# Power.net
KiCad netlist of a schematic drawn in Altium Designer
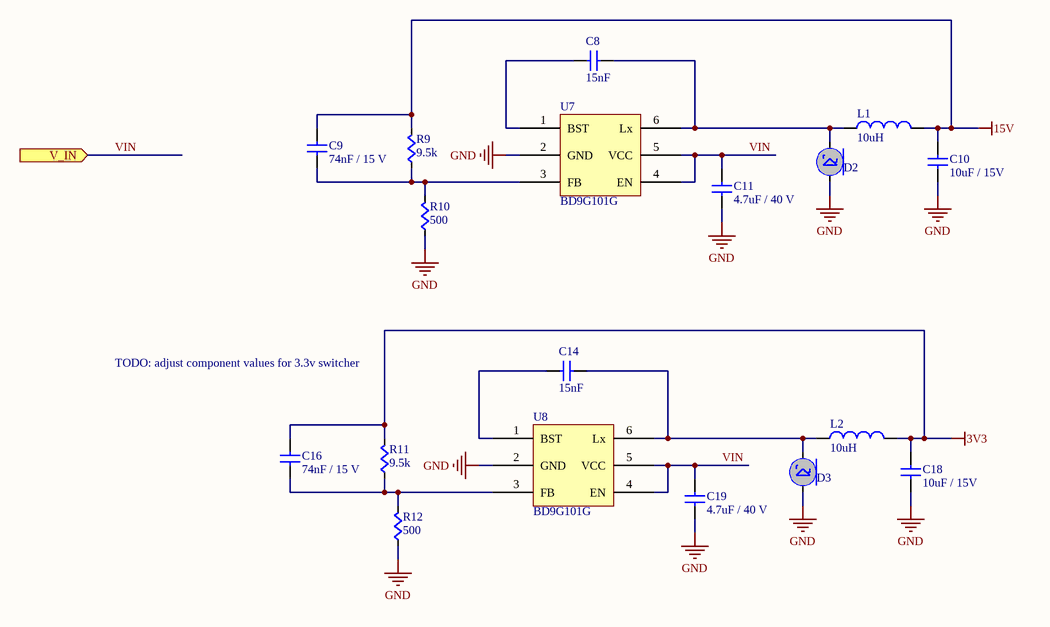
[diagram p0: Power.SchDoc]

(export (version "E")
  (design (tool "Eeschema 10.0.6"))
  (components
    (comp (ref "C8")
      (value "15nF")
      (footprint "CAPC0603")
      (fields (field (name "Comment") "Cap"))
      (libsource (lib "Passives") (part "Cap"))
    )
    (comp (ref "C9")
      (value "74nF / 15 V")
      (footprint "CAPC0603")
      (fields (field (name "Comment") "Cap"))
      (libsource (lib "Passives") (part "Cap"))
    )
    (comp (ref "C10")
      (value "10uF / 15V")
      (footprint "CAPC0805")
      (fields (field (name "Comment") "Cap"))
      (libsource (lib "Passives") (part "Cap"))
    )
    (comp (ref "C11")
      (value "4.7uF / 40 V")
      (footprint "CAPC0805")
      (fields (field (name "Comment") "Cap"))
      (libsource (lib "Passives") (part "Cap"))
    )
    (comp (ref "C14")
      (value "15nF")
      (footprint "CAPC0603")
      (fields (field (name "Comment") "Cap"))
      (libsource (lib "Passives") (part "Cap"))
    )
    (comp (ref "C16")
      (value "74nF / 15 V")
      (footprint "CAPC0603")
      (fields (field (name "Comment") "Cap"))
      (libsource (lib "Passives") (part "Cap"))
    )
    (comp (ref "C18")
      (value "10uF / 15V")
      (footprint "CAPC0805")
      (fields (field (name "Comment") "Cap"))
      (libsource (lib "Passives") (part "Cap"))
    )
    (comp (ref "C19")
      (value "4.7uF / 40 V")
      (footprint "CAPC0805")
      (fields (field (name "Comment") "Cap"))
      (libsource (lib "Passives") (part "Cap"))
    )
    (comp (ref "D2")
      (value "Schottky")
      (footprint "US1K-13-F")
      (description "Schottky Diode Template")
      (libsource (lib "Semiconductors") (part "Schottky"))
    )
    (comp (ref "D3")
      (value "Schottky")
      (footprint "US1K-13-F")
      (description "Schottky Diode Template")
      (libsource (lib "Semiconductors") (part "Schottky"))
    )
    (comp (ref "L1")
      (value "Inductor")
      (footprint "CAPC0805")
      (fields (field (name "INDUCTANCE") "10uH"))
      (libsource (lib "Passives") (part "Inductor"))
    )
    (comp (ref "L2")
      (value "Inductor")
      (footprint "CAPC0805")
      (fields (field (name "INDUCTANCE") "10uH"))
      (libsource (lib "Passives") (part "Inductor"))
    )
    (comp (ref "R9")
      (value "9.5k")
      (footprint "RES0603")
      (fields (field (name "Comment") "Res"))
      (libsource (lib "Passives") (part "Res"))
    )
    (comp (ref "R10")
      (value "500")
      (footprint "RES0603")
      (fields (field (name "Comment") "Res"))
      (libsource (lib "Passives") (part "Res"))
    )
    (comp (ref "R11")
      (value "9.5k")
      (footprint "RES0603")
      (fields (field (name "Comment") "Res"))
      (libsource (lib "Passives") (part "Res"))
    )
    (comp (ref "R12")
      (value "500")
      (footprint "RES0603")
      (fields (field (name "Comment") "Res"))
      (libsource (lib "Passives") (part "Res"))
    )
    (comp (ref "U7")
      (value "BD9G101G")
      (footprint "BD9G101G")
      (description "Simple Step-down Switching Regulators with Built-in Power MOSFET")
      (libsource (lib "ICs") (part "BD9G101G"))
    )
    (comp (ref "U8")
      (value "BD9G101G")
      (footprint "BD9G101G")
      (description "Simple Step-down Switching Regulators with Built-in Power MOSFET")
      (libsource (lib "ICs") (part "BD9G101G"))
    )
  )
  (nets
    (net (code "1") (name "/VIN") (class "Default")
      (node (ref "C11") (pin "1") (pinfunction "A_1") (pintype "passive"))
      (node (ref "C19") (pin "1") (pinfunction "A_1") (pintype "passive"))
      (node (ref "U7") (pin "4") (pinfunction "EN_4") (pintype "passive"))
      (node (ref "U7") (pin "5") (pinfunction "VCC_5") (pintype "passive"))
      (node (ref "U8") (pin "4") (pinfunction "EN_4") (pintype "passive"))
      (node (ref "U8") (pin "5") (pinfunction "VCC_5") (pintype "passive"))
    )
    (net (code "2") (name "3V3") (class "Default")
      (node (ref "C16") (pin "2") (pinfunction "B_2") (pintype "passive"))
      (node (ref "C18") (pin "1") (pinfunction "A_1") (pintype "passive"))
      (node (ref "L2") (pin "2") (pinfunction "B_2") (pintype "passive"))
      (node (ref "R11") (pin "1") (pinfunction "A_1") (pintype "passive"))
    )
    (net (code "3") (name "15V") (class "Default")
      (node (ref "C10") (pin "1") (pinfunction "A_1") (pintype "passive"))
      (node (ref "C9") (pin "2") (pinfunction "B_2") (pintype "passive"))
      (node (ref "L1") (pin "2") (pinfunction "B_2") (pintype "passive"))
      (node (ref "R9") (pin "1") (pinfunction "A_1") (pintype "passive"))
    )
    (net (code "4") (name "GND") (class "Default")
      (node (ref "C10") (pin "2") (pinfunction "B_2") (pintype "passive"))
      (node (ref "C11") (pin "2") (pinfunction "B_2") (pintype "passive"))
      (node (ref "C18") (pin "2") (pinfunction "B_2") (pintype "passive"))
      (node (ref "C19") (pin "2") (pinfunction "B_2") (pintype "passive"))
      (node (ref "D2") (pin "A") (pinfunction "A_A") (pintype "passive"))
      (node (ref "D3") (pin "A") (pinfunction "A_A") (pintype "passive"))
      (node (ref "R10") (pin "2") (pinfunction "B_2") (pintype "passive"))
      (node (ref "R12") (pin "2") (pinfunction "B_2") (pintype "passive"))
      (node (ref "U7") (pin "2") (pinfunction "GND_2") (pintype "passive"))
      (node (ref "U8") (pin "2") (pinfunction "GND_2") (pintype "passive"))
    )
    (net (code "5") (name "Net-(C8-A)") (class "Default")
      (node (ref "C8") (pin "1") (pinfunction "A_1") (pintype "passive"))
      (node (ref "U7") (pin "1") (pinfunction "BST_1") (pintype "passive"))
    )
    (net (code "6") (name "Net-(C8-B)") (class "Default")
      (node (ref "C8") (pin "2") (pinfunction "B_2") (pintype "passive"))
      (node (ref "D2") (pin "C") (pinfunction "C_C") (pintype "passive"))
      (node (ref "L1") (pin "1") (pinfunction "A_1") (pintype "passive"))
      (node (ref "U7") (pin "6") (pinfunction "Lx_6") (pintype "passive"))
    )
    (net (code "7") (name "Net-(C9-A)") (class "Default")
      (node (ref "C9") (pin "1") (pinfunction "A_1") (pintype "passive"))
      (node (ref "R10") (pin "1") (pinfunction "A_1") (pintype "passive"))
      (node (ref "R9") (pin "2") (pinfunction "B_2") (pintype "passive"))
      (node (ref "U7") (pin "3") (pinfunction "FB_3") (pintype "passive"))
    )
    (net (code "8") (name "Net-(C14-A)") (class "Default")
      (node (ref "C14") (pin "1") (pinfunction "A_1") (pintype "passive"))
      (node (ref "U8") (pin "1") (pinfunction "BST_1") (pintype "passive"))
    )
    (net (code "9") (name "Net-(C14-B)") (class "Default")
      (node (ref "C14") (pin "2") (pinfunction "B_2") (pintype "passive"))
      (node (ref "D3") (pin "C") (pinfunction "C_C") (pintype "passive"))
      (node (ref "L2") (pin "1") (pinfunction "A_1") (pintype "passive"))
      (node (ref "U8") (pin "6") (pinfunction "Lx_6") (pintype "passive"))
    )
    (net (code "10") (name "Net-(C16-A)") (class "Default")
      (node (ref "C16") (pin "1") (pinfunction "A_1") (pintype "passive"))
      (node (ref "R11") (pin "2") (pinfunction "B_2") (pintype "passive"))
      (node (ref "R12") (pin "1") (pinfunction "A_1") (pintype "passive"))
      (node (ref "U8") (pin "3") (pinfunction "FB_3") (pintype "passive"))
    )
  )
)
